# Sport_Analyzer_Teensy4_Mosfets.net
KiCad netlist of a schematic drawn in EAGLE
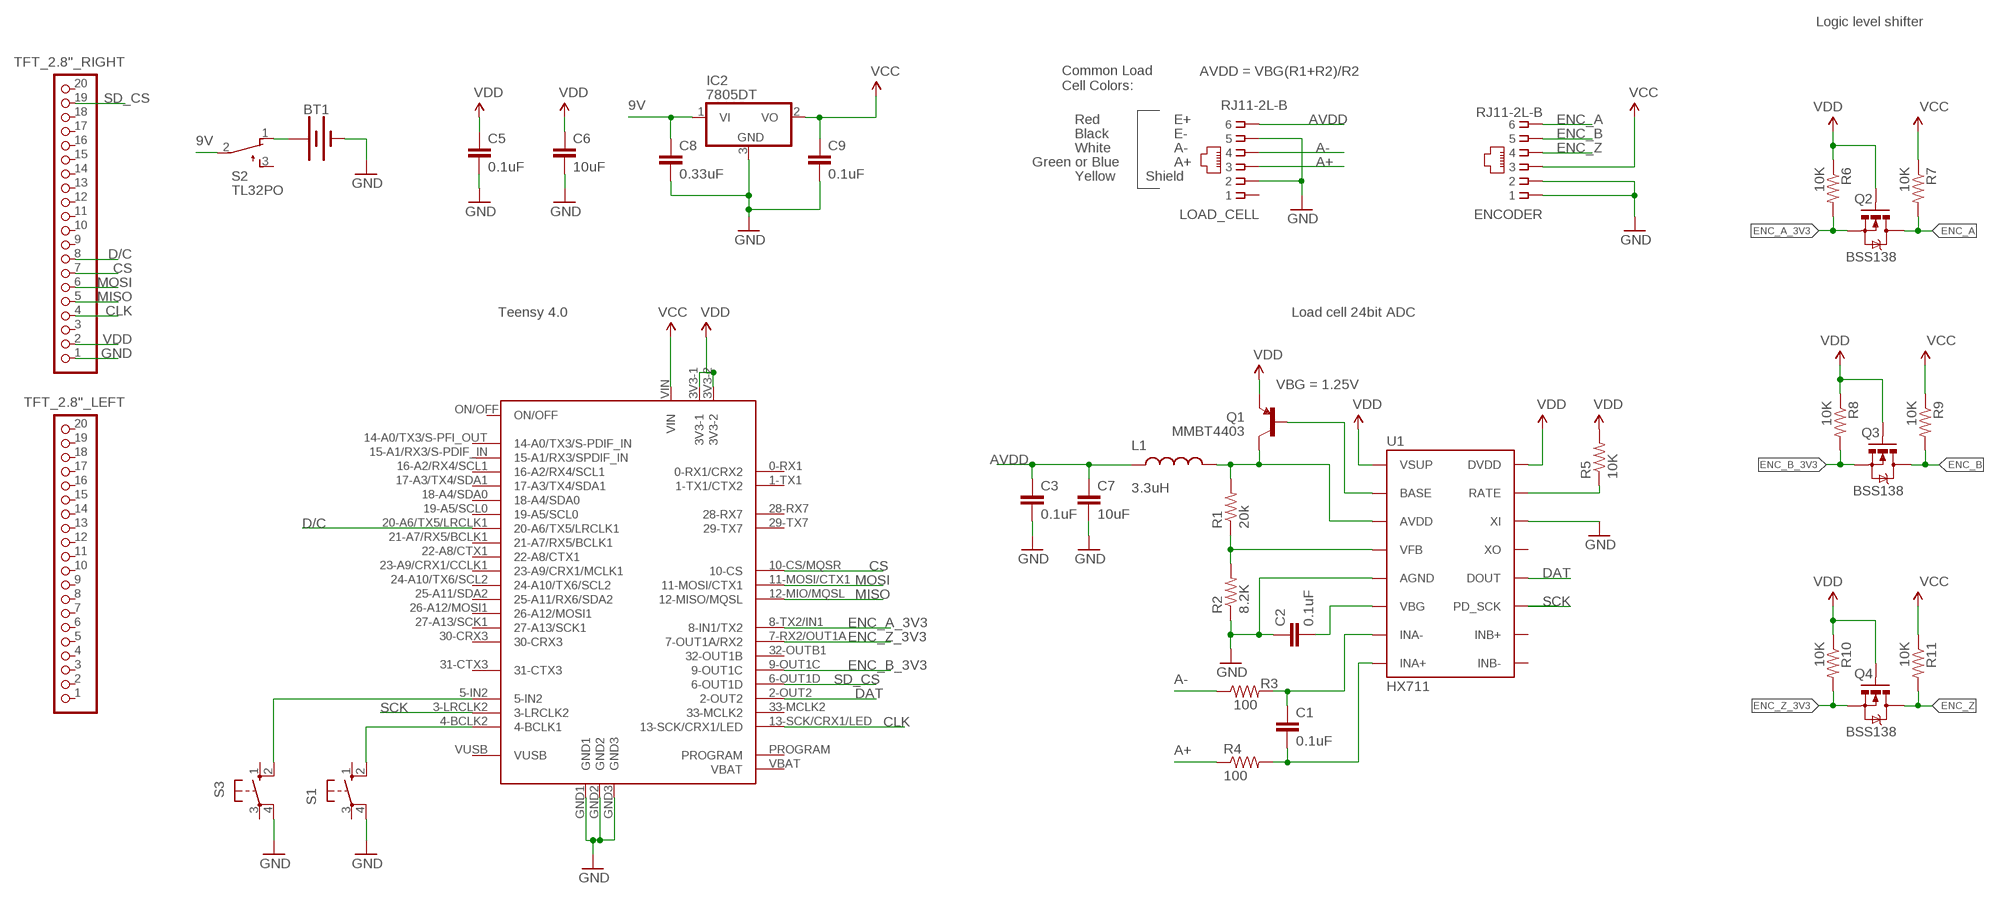
[diagram p0: schematic, sheet 1]

(export (version "E")
  (design (tool "Eeschema 10.0.6"))
  (components
    (comp (ref "BT1")
      (value "BATTERY-9V")
      (footprint "eagle-import:BATTCON_9V")
      (libsource (lib "eagle-import") (part "BATTERY-9V"))
    )
    (comp (ref "C1")
      (value "0.1uF")
      (footprint "eagle-import:0603-CAP")
      (libsource (lib "eagle-import") (part "0.1UF-25V-5%(0603)"))
    )
    (comp (ref "C2")
      (value "0.1uF")
      (footprint "eagle-import:0603-CAP")
      (libsource (lib "eagle-import") (part "0.1UF-25V-5%(0603)"))
    )
    (comp (ref "C3")
      (value "0.1uF")
      (footprint "eagle-import:0603-CAP")
      (libsource (lib "eagle-import") (part "0.1UF-25V-5%(0603)"))
    )
    (comp (ref "C5")
      (value "0.1uF")
      (footprint "eagle-import:0603-CAP")
      (libsource (lib "eagle-import") (part "0.1UF-25V-5%(0603)"))
    )
    (comp (ref "C6")
      (value "10uF")
      (footprint "eagle-import:1210")
      (libsource (lib "eagle-import") (part "10UF50V20%(1210)"))
    )
    (comp (ref "C7")
      (value "10uF")
      (footprint "eagle-import:1210")
      (libsource (lib "eagle-import") (part "10UF50V20%(1210)"))
    )
    (comp (ref "C8")
      (value "0.33uF")
      (footprint "eagle-import:0603-CAP")
      (libsource (lib "eagle-import") (part "0.1UF-25V-5%(0603)"))
    )
    (comp (ref "C9")
      (value "0.1uF")
      (footprint "eagle-import:0603-CAP")
      (libsource (lib "eagle-import") (part "0.1UF-25V-5%(0603)"))
    )
    (comp (ref "ENCODER")
      (value "RJ11-2L-B")
      (footprint "eagle-import:RJ11-NO_SHIELD")
      (fields (field (name "MF") "TYCO ELECTRONICS"))
      (libsource (lib "eagle-import") (part "RJ11-2L-B"))
    )
    (comp (ref "IC2")
      (value "7805DT")
      (footprint "eagle-import:TO252")
      (libsource (lib "eagle-import") (part "78DT05"))
    )
    (comp (ref "L1")
      (value "3.3uH")
      (footprint "eagle-import:0805")
      (libsource (lib "eagle-import") (part "INDUCTOR0805-IND"))
    )
    (comp (ref "LOAD_CELL")
      (value "RJ11-2L-B")
      (footprint "eagle-import:RJ11-NO_SHIELD")
      (fields (field (name "MF") "TYCO ELECTRONICS"))
      (libsource (lib "eagle-import") (part "RJ11-2L-B"))
    )
    (comp (ref "Q1")
      (value "MMBT4403")
      (footprint "eagle-import:SOT23-3")
      (libsource (lib "eagle-import") (part "TRANSISTOR_PNPMMBT4403"))
    )
    (comp (ref "Q2")
      (value "BSS138")
      (footprint "eagle-import:SOT23-3")
      (libsource (lib "eagle-import") (part "MOSFET-NCHANNELSMD"))
    )
    (comp (ref "Q3")
      (value "BSS138")
      (footprint "eagle-import:SOT23-3")
      (libsource (lib "eagle-import") (part "MOSFET-NCHANNELSMD"))
    )
    (comp (ref "Q4")
      (value "BSS138")
      (footprint "eagle-import:SOT23-3")
      (libsource (lib "eagle-import") (part "MOSFET-NCHANNELSMD"))
    )
    (comp (ref "R1")
      (value "20k")
      (footprint "eagle-import:0603-RES")
      (libsource (lib "eagle-import") (part "20KOHM1/10W1%(0603)"))
    )
    (comp (ref "R2")
      (value "8.2K")
      (footprint "eagle-import:0603-RES")
      (libsource (lib "eagle-import") (part "8.2KOHM-1/10W-5%(0603)"))
    )
    (comp (ref "R3")
      (value "100")
      (footprint "eagle-import:0603-RES")
      (libsource (lib "eagle-import") (part "100OHM-1/10W-1%(0603)"))
    )
    (comp (ref "R4")
      (value "100")
      (footprint "eagle-import:0603-RES")
      (libsource (lib "eagle-import") (part "100OHM-1/10W-1%(0603)"))
    )
    (comp (ref "R5")
      (value "10K")
      (footprint "eagle-import:0603-RES")
      (libsource (lib "eagle-import") (part "10KOHM-1/10W-1%(0603)0603"))
    )
    (comp (ref "R6")
      (value "10K")
      (footprint "eagle-import:0603-RES")
      (libsource (lib "eagle-import") (part "RESISTOR0603-RES"))
    )
    (comp (ref "R7")
      (value "10K")
      (footprint "eagle-import:0603-RES")
      (libsource (lib "eagle-import") (part "RESISTOR0603-RES"))
    )
    (comp (ref "R8")
      (value "10K")
      (footprint "eagle-import:0603-RES")
      (libsource (lib "eagle-import") (part "RESISTOR0603-RES"))
    )
    (comp (ref "R9")
      (value "10K")
      (footprint "eagle-import:0603-RES")
      (libsource (lib "eagle-import") (part "RESISTOR0603-RES"))
    )
    (comp (ref "R10")
      (value "10K")
      (footprint "eagle-import:0603-RES")
      (libsource (lib "eagle-import") (part "RESISTOR0603-RES"))
    )
    (comp (ref "R11")
      (value "10K")
      (footprint "eagle-import:0603-RES")
      (libsource (lib "eagle-import") (part "RESISTOR0603-RES"))
    )
    (comp (ref "S1")
      (value "10-XX")
      (footprint "eagle-import:B3F-10XX")
      (fields (field (name "MPN") "B3F-1000"))
      (libsource (lib "eagle-import") (part "10-XX"))
    )
    (comp (ref "S2")
      (value "TL32PO")
      (footprint "eagle-import:TL3XPO")
      (libsource (lib "eagle-import") (part "TL32PO"))
    )
    (comp (ref "S3")
      (value "10-XX")
      (footprint "eagle-import:B3F-10XX")
      (fields (field (name "MPN") "B3F-1000"))
      (libsource (lib "eagle-import") (part "10-XX"))
    )
    (comp (ref "TFT_2.8\"_LEFT")
      (value "PINHD-1X20")
      (footprint "eagle-import:1X20")
      (libsource (lib "eagle-import") (part "PINHD-1X20"))
    )
    (comp (ref "TFT_2.8\"_RIGHT")
      (value "PINHD-1X20")
      (footprint "eagle-import:1X20")
      (libsource (lib "eagle-import") (part "PINHD-1X20"))
    )
    (comp (ref "U$2")
      (value "TEENSY40")
      (footprint "eagle-import:TEENSY40")
      (libsource (lib "eagle-import") (part "TEENSY40"))
    )
    (comp (ref "U1")
      (value "HX711")
      (footprint "eagle-import:SO16")
      (libsource (lib "eagle-import") (part "HX711HX711"))
    )
  )
  (nets
    (net (code "1") (name "/9V") (class "Default")
      (node (ref "C8") (pin "1") (pinfunction "1_1") (pintype "passive"))
      (node (ref "IC2") (pin "1") (pinfunction "VI_1") (pintype "input"))
      (node (ref "S2") (pin "2") (pinfunction "P_2") (pintype "passive"))
    )
    (net (code "2") (name "/A+") (class "Default")
      (node (ref "LOAD_CELL") (pin "3") (pinfunction "3_3") (pintype "passive"))
      (node (ref "R4") (pin "1") (pinfunction "1_1") (pintype "passive"))
    )
    (net (code "3") (name "/A-") (class "Default")
      (node (ref "LOAD_CELL") (pin "4") (pinfunction "4_4") (pintype "passive"))
      (node (ref "R3") (pin "1") (pinfunction "1_1") (pintype "passive"))
    )
    (net (code "4") (name "/AVDD") (class "Default")
      (node (ref "C3") (pin "1") (pinfunction "1_1") (pintype "passive"))
      (node (ref "C7") (pin "1") (pinfunction "1_1") (pintype "passive"))
      (node (ref "L1") (pin "1") (pinfunction "1_1") (pintype "passive"))
      (node (ref "LOAD_CELL") (pin "6") (pinfunction "6_6") (pintype "passive"))
    )
    (net (code "5") (name "/CLK") (class "Default")
      (node (ref "TFT_2.8\"_RIGHT") (pin "4") (pinfunction "4_4") (pintype "passive"))
      (node (ref "U$2") (pin "13-SCK/CRX1/LED") (pinfunction "13-SCK/CRX1/LED_13-SCK/CRX1/LED") (pintype "bidirectional"))
    )
    (net (code "6") (name "/CS") (class "Default")
      (node (ref "TFT_2.8\"_RIGHT") (pin "7") (pinfunction "7_7") (pintype "passive"))
      (node (ref "U$2") (pin "10-CS/MQSR") (pinfunction "10-CS_10-CS/MQSR") (pintype "bidirectional"))
    )
    (net (code "7") (name "/DAT") (class "Default")
      (node (ref "U$2") (pin "2-OUT2") (pinfunction "2-OUT2_2-OUT2") (pintype "bidirectional"))
      (node (ref "U1") (pin "12") (pinfunction "DOUT_12") (pintype "bidirectional"))
    )
    (net (code "8") (name "/D{slash}C") (class "Default")
      (node (ref "TFT_2.8\"_RIGHT") (pin "8") (pinfunction "8_8") (pintype "passive"))
      (node (ref "U$2") (pin "20-A6/TX5/LRCLK1") (pinfunction "20-A6/TX5/LRCLK1_20-A6/TX5/LRCLK1") (pintype "bidirectional"))
    )
    (net (code "9") (name "/MISO") (class "Default")
      (node (ref "TFT_2.8\"_RIGHT") (pin "5") (pinfunction "5_5") (pintype "passive"))
      (node (ref "U$2") (pin "12-MIO/MQSL") (pinfunction "12-MISO/MQSL_12-MIO/MQSL") (pintype "bidirectional"))
    )
    (net (code "10") (name "/MOSI") (class "Default")
      (node (ref "TFT_2.8\"_RIGHT") (pin "6") (pinfunction "6_6") (pintype "passive"))
      (node (ref "U$2") (pin "11-MOSI/CTX1") (pinfunction "11-MOSI/CTX1_11-MOSI/CTX1") (pintype "bidirectional"))
    )
    (net (code "11") (name "/SCK") (class "Default")
      (node (ref "U$2") (pin "3-LRCLK2") (pinfunction "3-LRCLK2_3-LRCLK2") (pintype "bidirectional"))
      (node (ref "U1") (pin "11") (pinfunction "PD_SCK_11") (pintype "bidirectional"))
    )
    (net (code "12") (name "/SD_CS") (class "Default")
      (node (ref "TFT_2.8\"_RIGHT") (pin "19") (pinfunction "19_19") (pintype "passive"))
      (node (ref "U$2") (pin "6-OUT1D") (pinfunction "6-OUT1D_6-OUT1D") (pintype "bidirectional"))
    )
    (net (code "13") (name "ENC_A") (class "Default")
      (node (ref "ENCODER") (pin "6") (pinfunction "6_6") (pintype "passive"))
      (node (ref "Q2") (pin "3") (pinfunction "D_3") (pintype "passive"))
      (node (ref "R7") (pin "2") (pinfunction "2_2") (pintype "passive"))
    )
    (net (code "14") (name "ENC_A_3V3") (class "Default")
      (node (ref "Q2") (pin "2") (pinfunction "S_2") (pintype "passive"))
      (node (ref "R6") (pin "2") (pinfunction "2_2") (pintype "passive"))
      (node (ref "U$2") (pin "8-TX2/IN1") (pinfunction "8-IN1/TX2_8-TX2/IN1") (pintype "bidirectional"))
    )
    (net (code "15") (name "ENC_B") (class "Default")
      (node (ref "ENCODER") (pin "5") (pinfunction "5_5") (pintype "passive"))
      (node (ref "Q3") (pin "3") (pinfunction "D_3") (pintype "passive"))
      (node (ref "R9") (pin "2") (pinfunction "2_2") (pintype "passive"))
    )
    (net (code "16") (name "ENC_B_3V3") (class "Default")
      (node (ref "Q3") (pin "2") (pinfunction "S_2") (pintype "passive"))
      (node (ref "R8") (pin "2") (pinfunction "2_2") (pintype "passive"))
      (node (ref "U$2") (pin "9-OUT1C") (pinfunction "9-OUT1C_9-OUT1C") (pintype "bidirectional"))
    )
    (net (code "17") (name "ENC_Z") (class "Default")
      (node (ref "ENCODER") (pin "4") (pinfunction "4_4") (pintype "passive"))
      (node (ref "Q4") (pin "3") (pinfunction "D_3") (pintype "passive"))
      (node (ref "R11") (pin "2") (pinfunction "2_2") (pintype "passive"))
    )
    (net (code "18") (name "ENC_Z_3V3") (class "Default")
      (node (ref "Q4") (pin "2") (pinfunction "S_2") (pintype "passive"))
      (node (ref "R10") (pin "2") (pinfunction "2_2") (pintype "passive"))
      (node (ref "U$2") (pin "7-RX2/OUT1A") (pinfunction "7-OUT1A/RX2_7-RX2/OUT1A") (pintype "bidirectional"))
    )
    (net (code "19") (name "GND") (class "Default")
      (node (ref "BT1") (pin "-") (pinfunction "-_-") (pintype "power_in"))
      (node (ref "C2") (pin "1") (pinfunction "1_1") (pintype "passive"))
      (node (ref "C3") (pin "2") (pinfunction "2_2") (pintype "passive"))
      (node (ref "C5") (pin "2") (pinfunction "2_2") (pintype "passive"))
      (node (ref "C6") (pin "2") (pinfunction "2_2") (pintype "passive"))
      (node (ref "C7") (pin "2") (pinfunction "2_2") (pintype "passive"))
      (node (ref "C8") (pin "2") (pinfunction "2_2") (pintype "passive"))
      (node (ref "C9") (pin "2") (pinfunction "2_2") (pintype "passive"))
      (node (ref "ENCODER") (pin "1") (pinfunction "1_1") (pintype "passive"))
      (node (ref "ENCODER") (pin "2") (pinfunction "2_2") (pintype "passive"))
      (node (ref "IC2") (pin "3") (pinfunction "GND_3") (pintype "passive"))
      (node (ref "LOAD_CELL") (pin "2") (pinfunction "2_2") (pintype "passive"))
      (node (ref "LOAD_CELL") (pin "5") (pinfunction "5_5") (pintype "passive"))
      (node (ref "R2") (pin "1") (pinfunction "1_1") (pintype "passive"))
      (node (ref "S1") (pin "4") (pinfunction "P1_4") (pintype "passive"))
      (node (ref "S3") (pin "4") (pinfunction "P1_4") (pintype "passive"))
      (node (ref "TFT_2.8\"_RIGHT") (pin "1") (pinfunction "1_1") (pintype "passive"))
      (node (ref "U$2") (pin "GND1") (pinfunction "GND1_GND1") (pintype "bidirectional"))
      (node (ref "U$2") (pin "GND2") (pinfunction "GND2_GND2") (pintype "bidirectional"))
      (node (ref "U$2") (pin "GND3") (pinfunction "GND3_GND3") (pintype "bidirectional"))
      (node (ref "U1") (pin "14") (pinfunction "XI_14") (pintype "bidirectional"))
      (node (ref "U1") (pin "5") (pinfunction "AGND_5") (pintype "bidirectional"))
    )
    (net (code "20") (name "Net-(Q1-B)") (class "Default")
      (node (ref "Q1") (pin "1") (pinfunction "B_1") (pintype "passive"))
      (node (ref "U1") (pin "2") (pinfunction "BASE_2") (pintype "bidirectional"))
    )
    (net (code "21") (name "Net-(Q1-C)") (class "Default")
      (node (ref "L1") (pin "2") (pinfunction "2_2") (pintype "passive"))
      (node (ref "Q1") (pin "3") (pinfunction "C_3") (pintype "passive"))
      (node (ref "R1") (pin "2") (pinfunction "2_2") (pintype "passive"))
      (node (ref "U1") (pin "3") (pinfunction "AVDD_3") (pintype "bidirectional"))
    )
    (net (code "22") (name "Net-(S1-S1)") (class "Default")
      (node (ref "S1") (pin "2") (pinfunction "S1_2") (pintype "passive"))
      (node (ref "U$2") (pin "4-BCLK2") (pinfunction "4-BCLK1_4-BCLK2") (pintype "bidirectional"))
    )
    (net (code "23") (name "Net-(S2-O)") (class "Default")
      (node (ref "BT1") (pin "+") (pinfunction "+_+") (pintype "power_in"))
      (node (ref "S2") (pin "1") (pinfunction "O_1") (pintype "passive"))
    )
    (net (code "24") (name "Net-(S3-S1)") (class "Default")
      (node (ref "S3") (pin "2") (pinfunction "S1_2") (pintype "passive"))
      (node (ref "U$2") (pin "5-IN2") (pinfunction "5-IN2_5-IN2") (pintype "bidirectional"))
    )
    (net (code "25") (name "Net-(U1-INA+)") (class "Default")
      (node (ref "C1") (pin "2") (pinfunction "2_2") (pintype "passive"))
      (node (ref "R4") (pin "2") (pinfunction "2_2") (pintype "passive"))
      (node (ref "U1") (pin "8") (pinfunction "INA+_8") (pintype "bidirectional"))
    )
    (net (code "26") (name "Net-(U1-INA-)") (class "Default")
      (node (ref "C1") (pin "1") (pinfunction "1_1") (pintype "passive"))
      (node (ref "R3") (pin "2") (pinfunction "2_2") (pintype "passive"))
      (node (ref "U1") (pin "7") (pinfunction "INA-_7") (pintype "bidirectional"))
    )
    (net (code "27") (name "Net-(U1-RATE)") (class "Default")
      (node (ref "R5") (pin "1") (pinfunction "1_1") (pintype "passive"))
      (node (ref "U1") (pin "15") (pinfunction "RATE_15") (pintype "bidirectional"))
    )
    (net (code "28") (name "Net-(U1-VBG)") (class "Default")
      (node (ref "C2") (pin "2") (pinfunction "2_2") (pintype "passive"))
      (node (ref "U1") (pin "6") (pinfunction "VBG_6") (pintype "bidirectional"))
    )
    (net (code "29") (name "Net-(U1-VFB)") (class "Default")
      (node (ref "R1") (pin "1") (pinfunction "1_1") (pintype "passive"))
      (node (ref "R2") (pin "2") (pinfunction "2_2") (pintype "passive"))
      (node (ref "U1") (pin "4") (pinfunction "VFB_4") (pintype "bidirectional"))
    )
    (net (code "30") (name "VCC") (class "Default")
      (node (ref "C9") (pin "1") (pinfunction "1_1") (pintype "passive"))
      (node (ref "ENCODER") (pin "3") (pinfunction "3_3") (pintype "passive"))
      (node (ref "IC2") (pin "2") (pinfunction "VO_2") (pintype "passive"))
      (node (ref "R11") (pin "1") (pinfunction "1_1") (pintype "passive"))
      (node (ref "R7") (pin "1") (pinfunction "1_1") (pintype "passive"))
      (node (ref "R9") (pin "1") (pinfunction "1_1") (pintype "passive"))
      (node (ref "U$2") (pin "VIN") (pinfunction "VIN_VIN") (pintype "bidirectional"))
    )
    (net (code "31") (name "VDD") (class "Default")
      (node (ref "C5") (pin "1") (pinfunction "1_1") (pintype "passive"))
      (node (ref "C6") (pin "1") (pinfunction "1_1") (pintype "passive"))
      (node (ref "Q1") (pin "2") (pinfunction "E_2") (pintype "passive"))
      (node (ref "Q2") (pin "1") (pinfunction "G_1") (pintype "passive"))
      (node (ref "Q3") (pin "1") (pinfunction "G_1") (pintype "passive"))
      (node (ref "Q4") (pin "1") (pinfunction "G_1") (pintype "passive"))
      (node (ref "R10") (pin "1") (pinfunction "1_1") (pintype "passive"))
      (node (ref "R5") (pin "2") (pinfunction "2_2") (pintype "passive"))
      (node (ref "R6") (pin "1") (pinfunction "1_1") (pintype "passive"))
      (node (ref "R8") (pin "1") (pinfunction "1_1") (pintype "passive"))
      (node (ref "TFT_2.8\"_RIGHT") (pin "2") (pinfunction "2_2") (pintype "passive"))
      (node (ref "U$2") (pin "3V3-1") (pinfunction "3V3-1_3V3-1") (pintype "bidirectional"))
      (node (ref "U$2") (pin "3V3-2") (pinfunction "3V3-2_3V3-2") (pintype "bidirectional"))
      (node (ref "U1") (pin "1") (pinfunction "VSUP_1") (pintype "bidirectional"))
      (node (ref "U1") (pin "16") (pinfunction "DVDD_16") (pintype "bidirectional"))
    )
    (net (code "32") (name "unconnected-(LOAD_CELL-Pad1)") (class "Default")
      (node (ref "LOAD_CELL") (pin "1") (pinfunction "1_1") (pintype "passive"))
    )
    (net (code "33") (name "unconnected-(S1-P-Pad3)") (class "Default")
      (node (ref "S1") (pin "3") (pinfunction "P_3") (pintype "passive"))
    )
    (net (code "34") (name "unconnected-(S1-S-Pad1)") (class "Default")
      (node (ref "S1") (pin "1") (pinfunction "S_1") (pintype "passive"))
    )
    (net (code "35") (name "unconnected-(S2-S-Pad3)") (class "Default")
      (node (ref "S2") (pin "3") (pinfunction "S_3") (pintype "passive"))
    )
    (net (code "36") (name "unconnected-(S3-P-Pad3)") (class "Default")
      (node (ref "S3") (pin "3") (pinfunction "P_3") (pintype "passive"))
    )
    (net (code "37") (name "unconnected-(S3-S-Pad1)") (class "Default")
      (node (ref "S3") (pin "1") (pinfunction "S_1") (pintype "passive"))
    )
    (net (code "38") (name "unconnected-(TFT_2.8\"_LEFT-Pad1)") (class "Default")
      (node (ref "TFT_2.8\"_LEFT") (pin "1") (pinfunction "1_1") (pintype "passive"))
    )
    (net (code "39") (name "unconnected-(TFT_2.8\"_LEFT-Pad2)") (class "Default")
      (node (ref "TFT_2.8\"_LEFT") (pin "2") (pinfunction "2_2") (pintype "passive"))
    )
    (net (code "40") (name "unconnected-(TFT_2.8\"_LEFT-Pad3)") (class "Default")
      (node (ref "TFT_2.8\"_LEFT") (pin "3") (pinfunction "3_3") (pintype "passive"))
    )
    (net (code "41") (name "unconnected-(TFT_2.8\"_LEFT-Pad4)") (class "Default")
      (node (ref "TFT_2.8\"_LEFT") (pin "4") (pinfunction "4_4") (pintype "passive"))
    )
    (net (code "42") (name "unconnected-(TFT_2.8\"_LEFT-Pad5)") (class "Default")
      (node (ref "TFT_2.8\"_LEFT") (pin "5") (pinfunction "5_5") (pintype "passive"))
    )
    (net (code "43") (name "unconnected-(TFT_2.8\"_LEFT-Pad6)") (class "Default")
      (node (ref "TFT_2.8\"_LEFT") (pin "6") (pinfunction "6_6") (pintype "passive"))
    )
    (net (code "44") (name "unconnected-(TFT_2.8\"_LEFT-Pad7)") (class "Default")
      (node (ref "TFT_2.8\"_LEFT") (pin "7") (pinfunction "7_7") (pintype "passive"))
    )
    (net (code "45") (name "unconnected-(TFT_2.8\"_LEFT-Pad8)") (class "Default")
      (node (ref "TFT_2.8\"_LEFT") (pin "8") (pinfunction "8_8") (pintype "passive"))
    )
    (net (code "46") (name "unconnected-(TFT_2.8\"_LEFT-Pad9)") (class "Default")
      (node (ref "TFT_2.8\"_LEFT") (pin "9") (pinfunction "9_9") (pintype "passive"))
    )
    (net (code "47") (name "unconnected-(TFT_2.8\"_LEFT-Pad10)") (class "Default")
      (node (ref "TFT_2.8\"_LEFT") (pin "10") (pinfunction "10_10") (pintype "passive"))
    )
    (net (code "48") (name "unconnected-(TFT_2.8\"_LEFT-Pad11)") (class "Default")
      (node (ref "TFT_2.8\"_LEFT") (pin "11") (pinfunction "11_11") (pintype "passive"))
    )
    (net (code "49") (name "unconnected-(TFT_2.8\"_LEFT-Pad12)") (class "Default")
      (node (ref "TFT_2.8\"_LEFT") (pin "12") (pinfunction "12_12") (pintype "passive"))
    )
    (net (code "50") (name "unconnected-(TFT_2.8\"_LEFT-Pad13)") (class "Default")
      (node (ref "TFT_2.8\"_LEFT") (pin "13") (pinfunction "13_13") (pintype "passive"))
    )
    (net (code "51") (name "unconnected-(TFT_2.8\"_LEFT-Pad14)") (class "Default")
      (node (ref "TFT_2.8\"_LEFT") (pin "14") (pinfunction "14_14") (pintype "passive"))
    )
    (net (code "52") (name "unconnected-(TFT_2.8\"_LEFT-Pad15)") (class "Default")
      (node (ref "TFT_2.8\"_LEFT") (pin "15") (pinfunction "15_15") (pintype "passive"))
    )
    (net (code "53") (name "unconnected-(TFT_2.8\"_LEFT-Pad16)") (class "Default")
      (node (ref "TFT_2.8\"_LEFT") (pin "16") (pinfunction "16_16") (pintype "passive"))
    )
    (net (code "54") (name "unconnected-(TFT_2.8\"_LEFT-Pad17)") (class "Default")
      (node (ref "TFT_2.8\"_LEFT") (pin "17") (pinfunction "17_17") (pintype "passive"))
    )
    (net (code "55") (name "unconnected-(TFT_2.8\"_LEFT-Pad18)") (class "Default")
      (node (ref "TFT_2.8\"_LEFT") (pin "18") (pinfunction "18_18") (pintype "passive"))
    )
    (net (code "56") (name "unconnected-(TFT_2.8\"_LEFT-Pad19)") (class "Default")
      (node (ref "TFT_2.8\"_LEFT") (pin "19") (pinfunction "19_19") (pintype "passive"))
    )
    (net (code "57") (name "unconnected-(TFT_2.8\"_LEFT-Pad20)") (class "Default")
      (node (ref "TFT_2.8\"_LEFT") (pin "20") (pinfunction "20_20") (pintype "passive"))
    )
    (net (code "58") (name "unconnected-(TFT_2.8\"_RIGHT-Pad3)") (class "Default")
      (node (ref "TFT_2.8\"_RIGHT") (pin "3") (pinfunction "3_3") (pintype "passive"))
    )
    (net (code "59") (name "unconnected-(TFT_2.8\"_RIGHT-Pad9)") (class "Default")
      (node (ref "TFT_2.8\"_RIGHT") (pin "9") (pinfunction "9_9") (pintype "passive"))
    )
    (net (code "60") (name "unconnected-(TFT_2.8\"_RIGHT-Pad10)") (class "Default")
      (node (ref "TFT_2.8\"_RIGHT") (pin "10") (pinfunction "10_10") (pintype "passive"))
    )
    (net (code "61") (name "unconnected-(TFT_2.8\"_RIGHT-Pad11)") (class "Default")
      (node (ref "TFT_2.8\"_RIGHT") (pin "11") (pinfunction "11_11") (pintype "passive"))
    )
    (net (code "62") (name "unconnected-(TFT_2.8\"_RIGHT-Pad12)") (class "Default")
      (node (ref "TFT_2.8\"_RIGHT") (pin "12") (pinfunction "12_12") (pintype "passive"))
    )
    (net (code "63") (name "unconnected-(TFT_2.8\"_RIGHT-Pad13)") (class "Default")
      (node (ref "TFT_2.8\"_RIGHT") (pin "13") (pinfunction "13_13") (pintype "passive"))
    )
    (net (code "64") (name "unconnected-(TFT_2.8\"_RIGHT-Pad14)") (class "Default")
      (node (ref "TFT_2.8\"_RIGHT") (pin "14") (pinfunction "14_14") (pintype "passive"))
    )
    (net (code "65") (name "unconnected-(TFT_2.8\"_RIGHT-Pad15)") (class "Default")
      (node (ref "TFT_2.8\"_RIGHT") (pin "15") (pinfunction "15_15") (pintype "passive"))
    )
    (net (code "66") (name "unconnected-(TFT_2.8\"_RIGHT-Pad16)") (class "Default")
      (node (ref "TFT_2.8\"_RIGHT") (pin "16") (pinfunction "16_16") (pintype "passive"))
    )
    (net (code "67") (name "unconnected-(TFT_2.8\"_RIGHT-Pad17)") (class "Default")
      (node (ref "TFT_2.8\"_RIGHT") (pin "17") (pinfunction "17_17") (pintype "passive"))
    )
    (net (code "68") (name "unconnected-(TFT_2.8\"_RIGHT-Pad18)") (class "Default")
      (node (ref "TFT_2.8\"_RIGHT") (pin "18") (pinfunction "18_18") (pintype "passive"))
    )
    (net (code "69") (name "unconnected-(TFT_2.8\"_RIGHT-Pad20)") (class "Default")
      (node (ref "TFT_2.8\"_RIGHT") (pin "20") (pinfunction "20_20") (pintype "passive"))
    )
    (net (code "70") (name "unconnected-(U$2-0-RX1{slash}CRX2-Pad0-RX1)") (class "Default")
      (node (ref "U$2") (pin "0-RX1") (pinfunction "0-RX1/CRX2_0-RX1") (pintype "bidirectional"))
    )
    (net (code "71") (name "unconnected-(U$2-1-TX1{slash}CTX2-Pad1-TX1)") (class "Default")
      (node (ref "U$2") (pin "1-TX1") (pinfunction "1-TX1/CTX2_1-TX1") (pintype "bidirectional"))
    )
    (net (code "72") (name "unconnected-(U$2-14-A0{slash}TX3{slash}S-PDIF_IN-Pad14-A0{slash}TX3{slash}S-PFI_OUT)") (class "Default")
      (node (ref "U$2") (pin "14-A0/TX3/S-PFI_OUT") (pinfunction "14-A0/TX3/S-PDIF_IN_14-A0/TX3/S-PFI_OUT") (pintype "bidirectional"))
    )
    (net (code "73") (name "unconnected-(U$2-15-A1{slash}RX3{slash}SPDIF_IN-Pad15-A1{slash}RX3{slash}S-PDIF_IN)") (class "Default")
      (node (ref "U$2") (pin "15-A1/RX3/S-PDIF_IN") (pinfunction "15-A1/RX3/SPDIF_IN_15-A1/RX3/S-PDIF_IN") (pintype "bidirectional"))
    )
    (net (code "74") (name "unconnected-(U$2-23-A9{slash}CRX1{slash}MCLK1-Pad23-A9{slash}CRX1{slash}CCLK1)") (class "Default")
      (node (ref "U$2") (pin "23-A9/CRX1/CCLK1") (pinfunction "23-A9/CRX1/MCLK1_23-A9/CRX1/CCLK1") (pintype "bidirectional"))
    )
    (net (code "75") (name "unconnected-(U$2-25-A11{slash}RX6{slash}SDA2-Pad25-A11{slash}SDA2)") (class "Default")
      (node (ref "U$2") (pin "25-A11/SDA2") (pinfunction "25-A11/RX6/SDA2_25-A11/SDA2") (pintype "bidirectional"))
    )
    (net (code "76") (name "unconnected-(U$2-32-OUT1B-Pad32-OUTB1)") (class "Default")
      (node (ref "U$2") (pin "32-OUTB1") (pinfunction "32-OUT1B_32-OUTB1") (pintype "bidirectional"))
    )
    (net (code "77") (name "unconnected-(U$2-Pad16-A2{slash}RX4{slash}SCL1)") (class "Default")
      (node (ref "U$2") (pin "16-A2/RX4/SCL1") (pinfunction "16-A2/RX4/SCL1_16-A2/RX4/SCL1") (pintype "bidirectional"))
    )
    (net (code "78") (name "unconnected-(U$2-Pad17-A3{slash}TX4{slash}SDA1)") (class "Default")
      (node (ref "U$2") (pin "17-A3/TX4/SDA1") (pinfunction "17-A3/TX4/SDA1_17-A3/TX4/SDA1") (pintype "bidirectional"))
    )
    (net (code "79") (name "unconnected-(U$2-Pad18-A4{slash}SDA0)") (class "Default")
      (node (ref "U$2") (pin "18-A4/SDA0") (pinfunction "18-A4/SDA0_18-A4/SDA0") (pintype "bidirectional"))
    )
    (net (code "80") (name "unconnected-(U$2-Pad19-A5{slash}SCL0)") (class "Default")
      (node (ref "U$2") (pin "19-A5/SCL0") (pinfunction "19-A5/SCL0_19-A5/SCL0") (pintype "bidirectional"))
    )
    (net (code "81") (name "unconnected-(U$2-Pad21-A7{slash}RX5{slash}BCLK1)") (class "Default")
      (node (ref "U$2") (pin "21-A7/RX5/BCLK1") (pinfunction "21-A7/RX5/BCLK1_21-A7/RX5/BCLK1") (pintype "bidirectional"))
    )
    (net (code "82") (name "unconnected-(U$2-Pad22-A8{slash}CTX1)") (class "Default")
      (node (ref "U$2") (pin "22-A8/CTX1") (pinfunction "22-A8/CTX1_22-A8/CTX1") (pintype "bidirectional"))
    )
    (net (code "83") (name "unconnected-(U$2-Pad24-A10{slash}TX6{slash}SCL2)") (class "Default")
      (node (ref "U$2") (pin "24-A10/TX6/SCL2") (pinfunction "24-A10/TX6/SCL2_24-A10/TX6/SCL2") (pintype "bidirectional"))
    )
    (net (code "84") (name "unconnected-(U$2-Pad26-A12{slash}MOSI1)") (class "Default")
      (node (ref "U$2") (pin "26-A12/MOSI1") (pinfunction "26-A12/MOSI1_26-A12/MOSI1") (pintype "bidirectional"))
    )
    (net (code "85") (name "unconnected-(U$2-Pad27-A13{slash}SCK1)") (class "Default")
      (node (ref "U$2") (pin "27-A13/SCK1") (pinfunction "27-A13/SCK1_27-A13/SCK1") (pintype "bidirectional"))
    )
    (net (code "86") (name "unconnected-(U$2-Pad28-RX7)") (class "Default")
      (node (ref "U$2") (pin "28-RX7") (pinfunction "28-RX7_28-RX7") (pintype "bidirectional"))
    )
    (net (code "87") (name "unconnected-(U$2-Pad29-TX7)") (class "Default")
      (node (ref "U$2") (pin "29-TX7") (pinfunction "29-TX7_29-TX7") (pintype "bidirectional"))
    )
    (net (code "88") (name "unconnected-(U$2-Pad30-CRX3)") (class "Default")
      (node (ref "U$2") (pin "30-CRX3") (pinfunction "30-CRX3_30-CRX3") (pintype "bidirectional"))
    )
    (net (code "89") (name "unconnected-(U$2-Pad31-CTX3)") (class "Default")
      (node (ref "U$2") (pin "31-CTX3") (pinfunction "31-CTX3_31-CTX3") (pintype "bidirectional"))
    )
    (net (code "90") (name "unconnected-(U$2-Pad33-MCLK2)") (class "Default")
      (node (ref "U$2") (pin "33-MCLK2") (pinfunction "33-MCLK2_33-MCLK2") (pintype "bidirectional"))
    )
    (net (code "91") (name "unconnected-(U$2-PadON{slash}OFF)") (class "Default")
      (node (ref "U$2") (pin "ON/OFF") (pinfunction "ON/OFF_ON/OFF") (pintype "bidirectional"))
    )
    (net (code "92") (name "unconnected-(U$2-PadPROGRAM)") (class "Default")
      (node (ref "U$2") (pin "PROGRAM") (pinfunction "PROGRAM_PROGRAM") (pintype "bidirectional"))
    )
    (net (code "93") (name "unconnected-(U$2-PadVBAT)") (class "Default")
      (node (ref "U$2") (pin "VBAT") (pinfunction "VBAT_VBAT") (pintype "bidirectional"))
    )
    (net (code "94") (name "unconnected-(U$2-PadVUSB)") (class "Default")
      (node (ref "U$2") (pin "VUSB") (pinfunction "VUSB_VUSB") (pintype "bidirectional"))
    )
    (net (code "95") (name "unconnected-(U1-INB+-Pad10)") (class "Default")
      (node (ref "U1") (pin "10") (pinfunction "INB+_10") (pintype "bidirectional"))
    )
    (net (code "96") (name "unconnected-(U1-INB--Pad9)") (class "Default")
      (node (ref "U1") (pin "9") (pinfunction "INB-_9") (pintype "bidirectional"))
    )
    (net (code "97") (name "unconnected-(U1-XO-Pad13)") (class "Default")
      (node (ref "U1") (pin "13") (pinfunction "XO_13") (pintype "bidirectional"))
    )
  )
)
